# design.net
KiCad netlist of a schematic drawn in Altium Designer
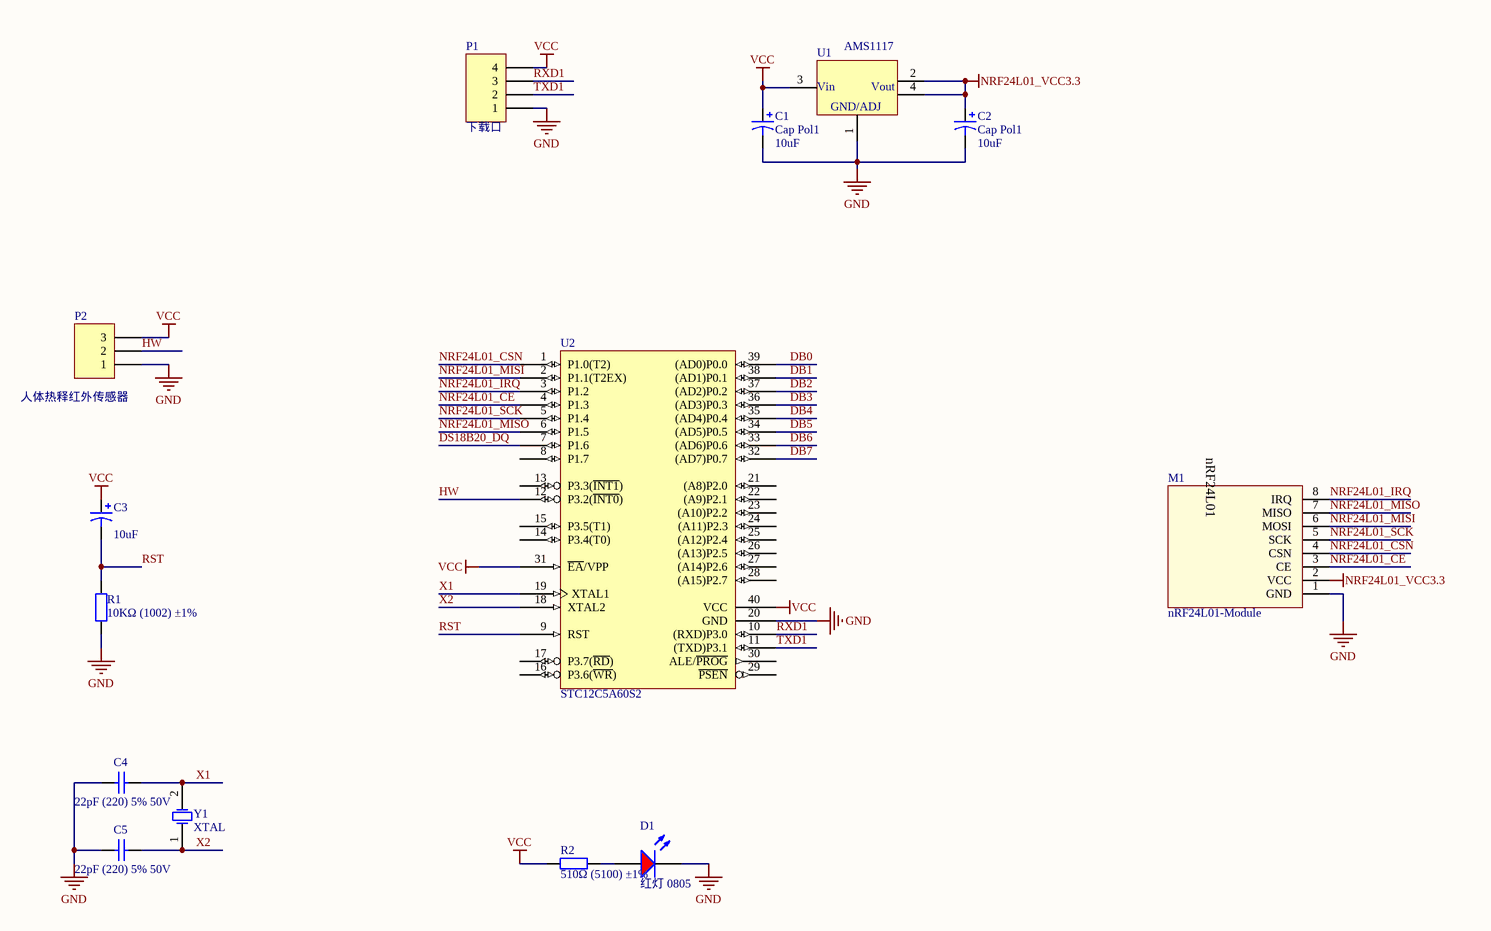
[diagram p0: 基于单片机的无线红外防盗报警系统原理图从机.SchDoc]

(export (version "E")
  (design (tool "Eeschema 10.0.6"))
  (components
    (comp (ref "C1")
      (value "Cap Pol1")
      (footprint "RB.2.5/.6.3mm")
      (description "Polarized Capacitor (Radial)")
      (fields (field (name "ALTIUM_VALUE") "10uF") (field (name "PUBLISHER") "Altium Limited"))
      (libsource (lib "Miscellaneous Devices") (part "Cap Pol1"))
    )
    (comp (ref "C2")
      (value "Cap Pol1")
      (footprint "RB.2.5/.6.3mm")
      (description "Polarized Capacitor (Radial)")
      (fields (field (name "ALTIUM_VALUE") "10uF") (field (name "PUBLISHER") "Altium Limited"))
      (libsource (lib "Miscellaneous Devices") (part "Cap Pol1"))
    )
    (comp (ref "C3")
      (value "10uF")
      (footprint "RB.2.5/.6.3mm")
      (description "Polarized Capacitor (Radial)")
      (fields (field (name "Comment") "Cap Pol1") (field (name "PUBLISHER") "Altium Limited"))
      (libsource (lib "Miscellaneous Devices") (part "Cap Pol1"))
    )
    (comp (ref "C4")
      (value "22pF (220) 5% 50V")
      (footprint "LC-0805_C")
      (description "贴片电容")
      (libsource (lib "Miscellaneous Devices LC") (part "0805 22pF (220) 5% 50V"))
    )
    (comp (ref "C5")
      (value "22pF (220) 5% 50V")
      (footprint "LC-0805_C")
      (description "贴片电容")
      (libsource (lib "Miscellaneous Devices LC") (part "0805 22pF (220) 5% 50V"))
    )
    (comp (ref "D1")
      (value "红灯 0805")
      (footprint "LC-0805_LED_S1")
      (description "发光二极管")
      (libsource (lib "Miscellaneous Devices LC") (part "0805 红灯"))
    )
    (comp (ref "M1")
      (value "nRF24L01-Module")
      (footprint "HDR2X4")
      (libsource (lib "个人") (part "nRF24L01-Module"))
    )
    (comp (ref "P1")
      (value "下载口")
      (footprint "HDR1X4")
      (description "Header, 4-Pin")
      (fields (field (name "PUBLISHER") "Altium Limited"))
      (libsource (lib "Miscellaneous Connectors") (part "Header 4"))
    )
    (comp (ref "P2")
      (value "人体热释红外传感器")
      (footprint "HDR1X3")
      (description "Header, 3-Pin")
      (fields (field (name "PUBLISHER") "Altium Limited"))
      (libsource (lib "Miscellaneous Connectors") (part "Header 3"))
    )
    (comp (ref "R1")
      (value "10KΩ (1002) ±1%")
      (footprint "LC-0805_R")
      (description "贴片电阻")
      (libsource (lib "Miscellaneous Devices LC") (part "0805 10KΩ (1002) 1%"))
    )
    (comp (ref "R2")
      (value "510Ω (5100) ±1%")
      (footprint "LC-0805_R")
      (description "贴片电阻")
      (libsource (lib "Miscellaneous Devices LC") (part "0805 510Ω (5100) 1%"))
    )
    (comp (ref "U1") (value "AMS1117") (footprint "LC-SOT-223") (libsource (lib "个人") (part "AMS1117")))
    (comp (ref "U2")
      (value "STC12C5A60S2")
      (footprint "DIP40")
      (description "8-Bit Microcontroller with 8K Flash ROM")
      (libsource (lib "Atmel Microcontroller 8051 Architecture") (part "AT89C52"))
    )
    (comp (ref "Y1")
      (value "XTAL")
      (footprint "R38")
      (description "Crystal Oscillator")
      (fields (field (name "PUBLISHER") "Altium Limited"))
      (libsource (lib "Miscellaneous Devices") (part "XTAL"))
    )
  )
  (nets
    (net (code "1") (name "/DB0") (class "Default")
      (node (ref "U2") (pin "39") (pinfunction "(AD0)P0.0_39") (pintype "bidirectional"))
    )
    (net (code "2") (name "/DB1") (class "Default")
      (node (ref "U2") (pin "38") (pinfunction "(AD1)P0.1_38") (pintype "bidirectional"))
    )
    (net (code "3") (name "/DB2") (class "Default")
      (node (ref "U2") (pin "37") (pinfunction "(AD2)P0.2_37") (pintype "bidirectional"))
    )
    (net (code "4") (name "/DB3") (class "Default")
      (node (ref "U2") (pin "36") (pinfunction "(AD3)P0.3_36") (pintype "bidirectional"))
    )
    (net (code "5") (name "/DB4") (class "Default")
      (node (ref "U2") (pin "35") (pinfunction "(AD4)P0.4_35") (pintype "bidirectional"))
    )
    (net (code "6") (name "/DB5") (class "Default")
      (node (ref "U2") (pin "34") (pinfunction "(AD5)P0.5_34") (pintype "bidirectional"))
    )
    (net (code "7") (name "/DB6") (class "Default")
      (node (ref "U2") (pin "33") (pinfunction "(AD6)P0.6_33") (pintype "bidirectional"))
    )
    (net (code "8") (name "/DB7") (class "Default")
      (node (ref "U2") (pin "32") (pinfunction "(AD7)P0.7_32") (pintype "bidirectional"))
    )
    (net (code "9") (name "/DS18B20_DQ") (class "Default")
      (node (ref "U2") (pin "7") (pinfunction "P1.6_7") (pintype "bidirectional"))
    )
    (net (code "10") (name "/HW") (class "Default")
      (node (ref "P2") (pin "2") (pinfunction "2_2") (pintype "passive"))
      (node (ref "U2") (pin "12") (pinfunction "P3.2(~{INT0})_12") (pintype "bidirectional"))
    )
    (net (code "11") (name "/NRF24L01_CE") (class "Default")
      (node (ref "M1") (pin "3") (pinfunction "CE_3") (pintype "passive"))
      (node (ref "U2") (pin "4") (pinfunction "P1.3_4") (pintype "bidirectional"))
    )
    (net (code "12") (name "/NRF24L01_CSN") (class "Default")
      (node (ref "M1") (pin "4") (pinfunction "CSN_4") (pintype "passive"))
      (node (ref "U2") (pin "1") (pinfunction "P1.0(T2)_1") (pintype "bidirectional"))
    )
    (net (code "13") (name "/NRF24L01_IRQ") (class "Default")
      (node (ref "M1") (pin "8") (pinfunction "IRQ_8") (pintype "passive"))
      (node (ref "U2") (pin "3") (pinfunction "P1.2_3") (pintype "bidirectional"))
    )
    (net (code "14") (name "/NRF24L01_MISI") (class "Default")
      (node (ref "M1") (pin "6") (pinfunction "MOSI_6") (pintype "passive"))
      (node (ref "U2") (pin "2") (pinfunction "P1.1(T2EX)_2") (pintype "bidirectional"))
    )
    (net (code "15") (name "/NRF24L01_MISO") (class "Default")
      (node (ref "M1") (pin "7") (pinfunction "MISO_7") (pintype "passive"))
      (node (ref "U2") (pin "6") (pinfunction "P1.5_6") (pintype "bidirectional"))
    )
    (net (code "16") (name "/NRF24L01_SCK") (class "Default")
      (node (ref "M1") (pin "5") (pinfunction "SCK_5") (pintype "passive"))
      (node (ref "U2") (pin "5") (pinfunction "P1.4_5") (pintype "bidirectional"))
    )
    (net (code "17") (name "/RST") (class "Default")
      (node (ref "C3") (pin "2") (pinfunction "2_2") (pintype "passive"))
      (node (ref "R1") (pin "2") (pinfunction "2_2") (pintype "passive"))
      (node (ref "U2") (pin "9") (pinfunction "RST_9") (pintype "input"))
    )
    (net (code "18") (name "/RXD1") (class "Default")
      (node (ref "P1") (pin "3") (pinfunction "3_3") (pintype "passive"))
      (node (ref "U2") (pin "10") (pinfunction "(RXD)P3.0_10") (pintype "bidirectional"))
    )
    (net (code "19") (name "/TXD1") (class "Default")
      (node (ref "P1") (pin "2") (pinfunction "2_2") (pintype "passive"))
      (node (ref "U2") (pin "11") (pinfunction "(TXD)P3.1_11") (pintype "bidirectional"))
    )
    (net (code "20") (name "/X1") (class "Default")
      (node (ref "C4") (pin "2") (pinfunction "2_2") (pintype "passive"))
      (node (ref "U2") (pin "19") (pinfunction "XTAL1_19") (pintype "input"))
      (node (ref "Y1") (pin "2") (pinfunction "OSC2_2") (pintype "passive"))
    )
    (net (code "21") (name "/X2") (class "Default")
      (node (ref "C5") (pin "2") (pinfunction "2_2") (pintype "passive"))
      (node (ref "U2") (pin "18") (pinfunction "XTAL2_18") (pintype "input"))
      (node (ref "Y1") (pin "1") (pinfunction "OSC1_1") (pintype "passive"))
    )
    (net (code "22") (name "GND") (class "Default")
      (node (ref "C1") (pin "2") (pinfunction "2_2") (pintype "passive"))
      (node (ref "C2") (pin "2") (pinfunction "2_2") (pintype "passive"))
      (node (ref "C4") (pin "1") (pinfunction "1_1") (pintype "passive"))
      (node (ref "C5") (pin "1") (pinfunction "1_1") (pintype "passive"))
      (node (ref "D1") (pin "K") (pinfunction "K_K") (pintype "passive"))
      (node (ref "M1") (pin "1") (pinfunction "GND_1") (pintype "passive"))
      (node (ref "P1") (pin "1") (pinfunction "1_1") (pintype "passive"))
      (node (ref "P2") (pin "1") (pinfunction "1_1") (pintype "passive"))
      (node (ref "R1") (pin "1") (pinfunction "1_1") (pintype "passive"))
      (node (ref "U1") (pin "1") (pintype "passive"))
      (node (ref "U2") (pin "20") (pinfunction "GND_20") (pintype "power_in"))
    )
    (net (code "23") (name "NRF24L01_VCC3.3") (class "Default")
      (node (ref "C2") (pin "1") (pinfunction "1_1") (pintype "passive"))
      (node (ref "M1") (pin "2") (pinfunction "VCC_2") (pintype "passive"))
      (node (ref "U1") (pin "2") (pintype "passive"))
      (node (ref "U1") (pin "4") (pintype "passive"))
    )
    (net (code "24") (name "Net-(D1-PadA)") (class "Default")
      (node (ref "D1") (pin "A") (pinfunction "A_A") (pintype "passive"))
      (node (ref "R2") (pin "2") (pinfunction "2_2") (pintype "passive"))
    )
    (net (code "25") (name "VCC") (class "Default")
      (node (ref "C1") (pin "1") (pinfunction "1_1") (pintype "passive"))
      (node (ref "C3") (pin "1") (pinfunction "1_1") (pintype "passive"))
      (node (ref "P1") (pin "4") (pinfunction "4_4") (pintype "passive"))
      (node (ref "P2") (pin "3") (pinfunction "3_3") (pintype "passive"))
      (node (ref "R2") (pin "1") (pinfunction "1_1") (pintype "passive"))
      (node (ref "U1") (pin "3") (pintype "passive"))
      (node (ref "U2") (pin "31") (pinfunction "~{EA}/VPP_31") (pintype "input"))
      (node (ref "U2") (pin "40") (pinfunction "VCC_40") (pintype "power_in"))
    )
    (net (code "26") (name "unconnected-(U2-(A8)P2.0-Pad21)") (class "Default")
      (node (ref "U2") (pin "21") (pinfunction "(A8)P2.0_21") (pintype "bidirectional"))
    )
    (net (code "27") (name "unconnected-(U2-(A9)P2.1-Pad22)") (class "Default")
      (node (ref "U2") (pin "22") (pinfunction "(A9)P2.1_22") (pintype "bidirectional"))
    )
    (net (code "28") (name "unconnected-(U2-(A10)P2.2-Pad23)") (class "Default")
      (node (ref "U2") (pin "23") (pinfunction "(A10)P2.2_23") (pintype "bidirectional"))
    )
    (net (code "29") (name "unconnected-(U2-(A11)P2.3-Pad24)") (class "Default")
      (node (ref "U2") (pin "24") (pinfunction "(A11)P2.3_24") (pintype "bidirectional"))
    )
    (net (code "30") (name "unconnected-(U2-(A12)P2.4-Pad25)") (class "Default")
      (node (ref "U2") (pin "25") (pinfunction "(A12)P2.4_25") (pintype "bidirectional"))
    )
    (net (code "31") (name "unconnected-(U2-(A13)P2.5-Pad26)") (class "Default")
      (node (ref "U2") (pin "26") (pinfunction "(A13)P2.5_26") (pintype "bidirectional"))
    )
    (net (code "32") (name "unconnected-(U2-(A14)P2.6-Pad27)") (class "Default")
      (node (ref "U2") (pin "27") (pinfunction "(A14)P2.6_27") (pintype "bidirectional"))
    )
    (net (code "33") (name "unconnected-(U2-(A15)P2.7-Pad28)") (class "Default")
      (node (ref "U2") (pin "28") (pinfunction "(A15)P2.7_28") (pintype "bidirectional"))
    )
    (net (code "34") (name "unconnected-(U2-ALE{slash}~{PROG}-Pad30)") (class "Default")
      (node (ref "U2") (pin "30") (pinfunction "ALE/~{PROG}_30") (pintype "output"))
    )
    (net (code "35") (name "unconnected-(U2-P1.7-Pad8)") (class "Default")
      (node (ref "U2") (pin "8") (pinfunction "P1.7_8") (pintype "bidirectional"))
    )
    (net (code "36") (name "unconnected-(U2-P3.3(~{INT1})-Pad13)") (class "Default")
      (node (ref "U2") (pin "13") (pinfunction "P3.3(~{INT1})_13") (pintype "bidirectional"))
    )
    (net (code "37") (name "unconnected-(U2-P3.4(T0)-Pad14)") (class "Default")
      (node (ref "U2") (pin "14") (pinfunction "P3.4(T0)_14") (pintype "bidirectional"))
    )
    (net (code "38") (name "unconnected-(U2-P3.5(T1)-Pad15)") (class "Default")
      (node (ref "U2") (pin "15") (pinfunction "P3.5(T1)_15") (pintype "bidirectional"))
    )
    (net (code "39") (name "unconnected-(U2-P3.6(~{WR})-Pad16)") (class "Default")
      (node (ref "U2") (pin "16") (pinfunction "P3.6(~{WR})_16") (pintype "bidirectional"))
    )
    (net (code "40") (name "unconnected-(U2-P3.7(~{RD})-Pad17)") (class "Default")
      (node (ref "U2") (pin "17") (pinfunction "P3.7(~{RD})_17") (pintype "bidirectional"))
    )
    (net (code "41") (name "unconnected-(U2-~{PSEN}-Pad29)") (class "Default")
      (node (ref "U2") (pin "29") (pinfunction "~{PSEN}_29") (pintype "output"))
    )
  )
)
